# Receiver-Sheet.net
KiCad netlist of a schematic drawn in Altium Designer
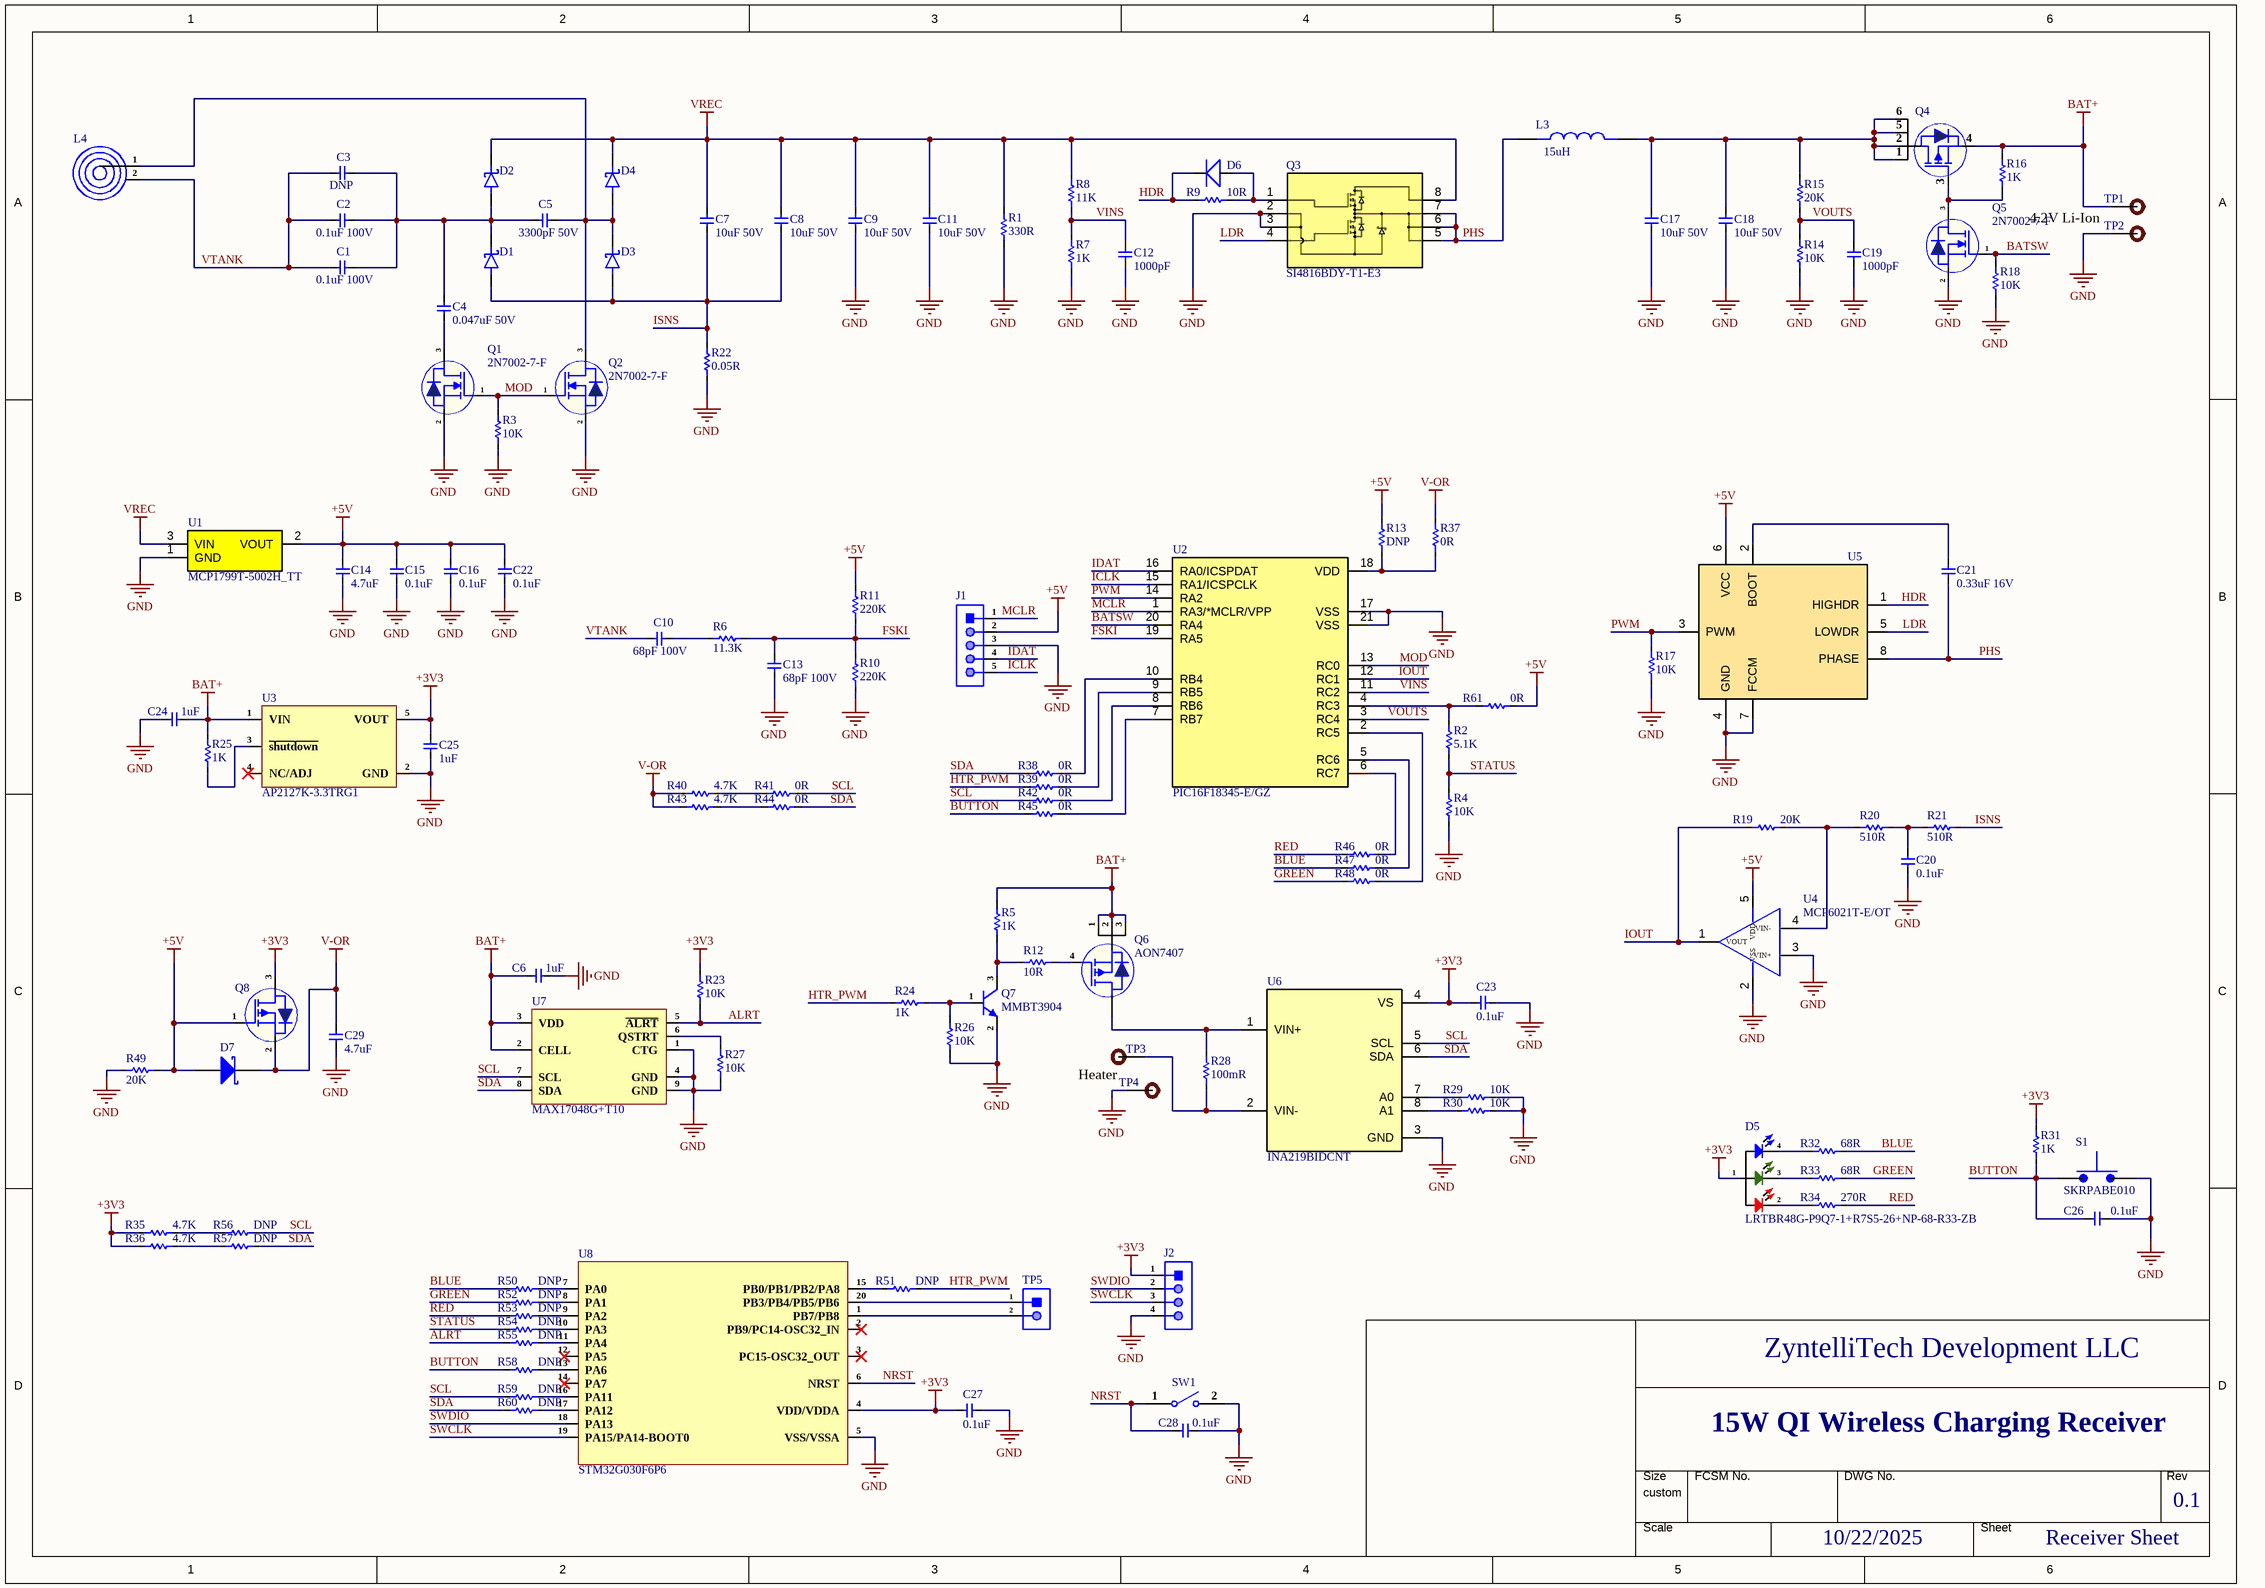
[diagram p0: Receiver-Sheet.SchDoc]

(export (version "E")
  (design (tool "Eeschema 10.0.6"))
  (components
    (comp (ref "C1")
      (value "0.1uF 100V")
      (footprint "Cap-1206")
      (description "CC1206KKX7R0BB104 - CAP CER 0.1uF 100V 10% X7R SMD 1206")
      (libsource (lib "Schlib1") (part "CAP-1206"))
    )
    (comp (ref "C2")
      (value "0.1uF 100V")
      (footprint "Cap-1206")
      (description "CC1206KKX7R0BB104 - CAP CER 0.1uF 100V 10% X7R SMD 1206")
      (libsource (lib "Schlib1") (part "CAP-1206"))
    )
    (comp (ref "C3")
      (value "DNP")
      (footprint "Cap-1206")
      (description "CC1206KKX7R0BB104 - CAP CER 0.1uF 100V 10% X7R SMD 1206")
      (libsource (lib "Schlib1") (part "CAP-1206"))
    )
    (comp (ref "C4")
      (value "0.047uF 50V")
      (footprint "Cap-0805")
      (description "C0805C473K5RACTU - CAP CER 0.047uF 50V 10% X7R SMD 0805")
      (libsource (lib "Schlib1") (part "CAP-0805"))
    )
    (comp (ref "C5")
      (value "3300pF 50V")
      (footprint "Cap-0805")
      (description "885012007066 - CAP CER 3300pF 50V 5% NP0 SMD 0805")
      (libsource (lib "Schlib1") (part "CAP-0805"))
    )
    (comp (ref "C6") (value "1uF") (footprint "Cap-0603") (libsource (lib "Schlib1") (part "CAP-0603")))
    (comp (ref "C7")
      (value "10uF 50V")
      (footprint "Cap-1210")
      (description "UMK325AB7106MM - CAP CER 10uF 50V 20% X7R SMD 1210")
      (libsource (lib "Schlib1") (part "CAP-1210"))
    )
    (comp (ref "C8")
      (value "10uF 50V")
      (footprint "Cap-1210")
      (description "UMK325AB7106MM - CAP CER 10uF 50V 20% X7R SMD 1210")
      (libsource (lib "Schlib1") (part "CAP-1210"))
    )
    (comp (ref "C9")
      (value "10uF 50V")
      (footprint "Cap-1210")
      (description "UMK325AB7106MM - CAP CER 10uF 50V 20% X7R SMD 1210")
      (libsource (lib "Schlib1") (part "CAP-1210"))
    )
    (comp (ref "C10")
      (value "68pF 100V")
      (footprint "Cap-0603")
      (description "C0603C680J1GACTU - CAP CER 68pF 100V 5% C0G SMD 0603")
      (libsource (lib "Schlib1") (part "CAP-0603"))
    )
    (comp (ref "C11")
      (value "10uF 50V")
      (footprint "Cap-1210")
      (description "UMK325AB7106MM - CAP CER 10uF 50V 20% X7R SMD 1210")
      (libsource (lib "Schlib1") (part "CAP-1210"))
    )
    (comp (ref "C12")
      (value "1000pF")
      (footprint "Cap-0603")
      (description "NMC0603X7R102K50TRPF - CAP CER 1000pF 50V 20% X7R SMD 0603")
      (libsource (lib "Schlib1") (part "CAP-0603"))
    )
    (comp (ref "C13")
      (value "68pF 100V")
      (footprint "Cap-0603")
      (description "C0603C680J1GACTU - CAP CER 68pF 100V 5% C0G SMD 0603")
      (libsource (lib "Schlib1") (part "CAP-0603"))
    )
    (comp (ref "C14")
      (value "4.7uF")
      (footprint "Cap-0805")
      (description "C2012X5R1E475M125AB - CAP CER 4.7uF 25V 20% X5R SMD 0805")
      (libsource (lib "Schlib1") (part "CAP-0805"))
    )
    (comp (ref "C15")
      (value "0.1uF")
      (footprint "Cap-0603")
      (description "06033C104JAT2A - CAP CER 0.1uF 25V 5% X7R SMD 0603")
      (libsource (lib "Schlib1") (part "CAP-0603"))
    )
    (comp (ref "C16")
      (value "0.1uF")
      (footprint "Cap-0603")
      (description "06033C104JAT2A - CAP CER 0.1uF 25V 5% X7R SMD 0603")
      (libsource (lib "Schlib1") (part "CAP-0603"))
    )
    (comp (ref "C17")
      (value "10uF 50V")
      (footprint "Cap-1210")
      (description "UMK325AB7106MM - CAP CER 10uF 50V 20% X7R SMD 1210")
      (libsource (lib "Schlib1") (part "CAP-1210"))
    )
    (comp (ref "C18")
      (value "10uF 50V")
      (footprint "Cap-1210")
      (description "UMK325AB7106MM - CAP CER 10uF 50V 20% X7R SMD 1210")
      (libsource (lib "Schlib1") (part "CAP-1210"))
    )
    (comp (ref "C19")
      (value "1000pF")
      (footprint "Cap-0603")
      (description "NMC0603X7R102K50TRPF - CAP CER 1000pF 50V 20% X7R SMD 0603")
      (libsource (lib "Schlib1") (part "CAP-0603"))
    )
    (comp (ref "C20")
      (value "0.1uF")
      (footprint "Cap-0603")
      (description "CL10B104KO8NNNC - CAP CER 0.1uF 16V 10% X7R SMD 0603")
      (libsource (lib "Schlib1") (part "CAP-0603"))
    )
    (comp (ref "C21")
      (value "0.33uF 16V")
      (footprint "Cap-0603")
      (description "885012206049 - CAP CER 0.33uF 16V 10% X7R SMD 0603")
      (libsource (lib "Schlib1") (part "CAP-0603"))
    )
    (comp (ref "C22")
      (value "0.1uF")
      (footprint "Cap-0603")
      (description "06033C104JAT2A - CAP CER 0.1uF 25V 5% X7R SMD 0603")
      (libsource (lib "Schlib1") (part "CAP-0603"))
    )
    (comp (ref "C23")
      (value "0.1uF")
      (footprint "Cap-0603")
      (description "CL10B104KO8NNNC - CAP CER 0.1uF 16V 10% X7R SMD 0603")
      (libsource (lib "Schlib1") (part "CAP-0603"))
    )
    (comp (ref "C24") (value "1uF") (footprint "Cap-0603") (libsource (lib "Schlib1") (part "CAP-0603")))
    (comp (ref "C25") (value "1uF") (footprint "Cap-0603") (libsource (lib "Schlib1") (part "CAP-0603")))
    (comp (ref "C26")
      (value "0.1uF")
      (footprint "Cap-0603")
      (description "06033C104JAT2A - CAP CER 0.1uF 25V 5% X7R SMD 0603")
      (libsource (lib "Schlib1") (part "CAP-0603"))
    )
    (comp (ref "C27")
      (value "0.1uF")
      (footprint "Cap-0603")
      (description "CL10B104KO8NNNC - CAP CER 0.1uF 16V 10% X7R SMD 0603")
      (libsource (lib "Schlib1") (part "CAP-0603"))
    )
    (comp (ref "C28")
      (value "0.1uF")
      (footprint "Cap-0603")
      (description "CL10B104KO8NNNC - CAP CER 0.1uF 16V 10% X7R SMD 0603")
      (libsource (lib "Schlib1") (part "CAP-0603"))
    )
    (comp (ref "C29")
      (value "4.7uF")
      (footprint "Cap-0805")
      (description "C2012X5R1E475M125AB - CAP CER 4.7uF 25V 20% X5R SMD 0805")
      (libsource (lib "Schlib1") (part "CAP-0805"))
    )
    (comp (ref "D1")
      (value "PMEG6045ETPX")
      (footprint "DIO_PMEG6045ETPX")
      (description "Rectifier Diode Schottky 4.5A 20ns Automotive 2-Pin SOD-128 T/R")
      (fields (field (name "MF") "Nexperia"))
      (libsource (lib "Schlib1") (part "PMEG6045ETPX"))
    )
    (comp (ref "D2")
      (value "PMEG6045ETPX")
      (footprint "DIO_PMEG6045ETPX")
      (description "Rectifier Diode Schottky 4.5A 20ns Automotive 2-Pin SOD-128 T/R")
      (fields (field (name "MF") "Nexperia"))
      (libsource (lib "Schlib1") (part "PMEG6045ETPX"))
    )
    (comp (ref "D3")
      (value "PMEG6045ETPX")
      (footprint "DIO_PMEG6045ETPX")
      (description "Rectifier Diode Schottky 4.5A 20ns Automotive 2-Pin SOD-128 T/R")
      (fields (field (name "MF") "Nexperia"))
      (libsource (lib "Schlib1") (part "PMEG6045ETPX"))
    )
    (comp (ref "D4")
      (value "PMEG6045ETPX")
      (footprint "DIO_PMEG6045ETPX")
      (description "Rectifier Diode Schottky 4.5A 20ns Automotive 2-Pin SOD-128 T/R")
      (fields (field (name "MF") "Nexperia"))
      (libsource (lib "Schlib1") (part "PMEG6045ETPX"))
    )
    (comp (ref "D5")
      (value "LRTBR48G-P9Q7-1+R7S5-26+NP-68-R33-ZB")
      (footprint "LRTBR48G-P9Q7-1+R7S5-26+NP-68-R33-ZB")
      (libsource (lib "Schlib1") (part "LRTBR48G-P9Q7-1+R7S5-26+NP-68-R33-ZB"))
    )
    (comp (ref "D6")
      (value "BAT54JFILM")
      (footprint "SOD-323")
      (fields (field (name "MF") "STMicroelectronics"))
      (libsource (lib "Schlib1") (part "BAT54JFILM"))
    )
    (comp (ref "D7")
      (value "MBR120VLSFT3G")
      (footprint "SOD-123")
      (description "DIODE SCHOTTKY 20V 1A SOD123FL")
      (fields (field (name "MANUFACTURER") "ON Semiconductor") (field (name "LCSC PART NUMBER") "C295749"))
      (libsource (lib "Schlib1") (part "MBR120VLSFT3G"))
    )
    (comp (ref "J1")
      (value "X6511WV-05H-C60D30")
      (footprint "HDR1X5_")
      (fields (field (name "MANUFACTURER") "XKB") (field (name "LCSC PART NUMBER") "C706877"))
      (libsource (lib "Schlib1") (part "X6511WV-05H-C60D30"))
    )
    (comp (ref "J2")
      (value "X6511WV-04H-C60D30")
      (footprint "HDR1X4_")
      (fields (field (name "MANUFACTURER") "XKB") (field (name "LCSC PART NUMBER") "C706876"))
      (libsource (lib "Schlib1") (part "X6511WV-04H-C60D30"))
    )
    (comp (ref "L3")
      (value "15uH")
      (footprint "IND_XAL6060-153MEB")
      (description "Power inductor, shielded, 20% tol, SMT, RoHS, halogen f")
      (fields (field (name "MF") "Coilcraft") (field (name "MP") "XAL6060-153MEB"))
      (libsource (lib "Schlib1") (part "XAL6060-153MEB"))
    )
    (comp (ref "L4")
      (value "760308102207")
      (footprint "WE-WPCC_RX_760308102207")
      (description "RX 1 COIL 1 LYR BIFILAR 8UH 5A")
      (fields (field (name "MF") "WÃ¼rth Elektronik"))
      (libsource (lib "Schlib1") (part "760308102207"))
    )
    (comp (ref "Q1")
      (value "2N7002-7-F")
      (footprint "SOT103P240X110-3N")
      (description "N-Channel 60 V 115mA (Ta) 370mW (Ta) Surface Mount SOT-23-3")
      (fields (field (name "MF") "Diodes Inc."))
      (libsource (lib "Schlib1") (part "2N7002-7-F"))
    )
    (comp (ref "Q2")
      (value "2N7002-7-F")
      (footprint "SOT103P240X110-3N")
      (description "N-Channel 60 V 115mA (Ta) 370mW (Ta) Surface Mount SOT-23-3")
      (fields (field (name "MF") "Diodes Inc."))
      (libsource (lib "Schlib1") (part "2N7002-7-F"))
    )
    (comp (ref "Q3")
      (value "SI4816BDY-T1-E3")
      (footprint "SOIC8_NARROW_VIS")
      (description "DUAL N-CH 30-V (D-S) MOSFET W/SCHOTTKY")
      (libsource (lib "Schlib1") (part "SI4816BDY-T1-E3"))
    )
    (comp (ref "Q4")
      (value "SI3433CDV-T1-GE3")
      (footprint "6-TSOP_")
      (libsource (lib "Schlib1") (part "SI3433CDV-T1-GE3"))
    )
    (comp (ref "Q5")
      (value "2N7002-7-F")
      (footprint "SOT103P240X110-3N")
      (description "N-Channel 60 V 115mA (Ta) 370mW (Ta) Surface Mount SOT-23-3")
      (fields (field (name "MF") "Diodes Inc."))
      (libsource (lib "Schlib1") (part "2N7002-7-F"))
    )
    (comp (ref "Q6")
      (value "AON7407")
      (footprint "TRANS_AON7407")
      (description "P-Channel 20 V 14.5A (Ta), 40A (Tc) 3.1W (Ta), 29W (Tc) Surface Mount 8-DFN-EP (3x3)")
      (fields (field (name "MF") "Alpha & Omega Semiconductor Inc."))
      (libsource (lib "Schlib1") (part "AON7407"))
    )
    (comp (ref "Q7")
      (value "MMBT3904")
      (footprint "SOT-23")
      (description "40V 200mW 100 200mA NPN SOT-23 Bipolar (BJT) ROHS")
      (fields (field (name "MANUFACTURER") "ElecSuper") (field (name "LCSC PART NUMBER") "C5249683"))
      (libsource (lib "Schlib1") (part "MMBT3904"))
    )
    (comp (ref "Q8")
      (value "DMG3415U")
      (footprint "SOT-23")
      (description "P-Channel MOSFETs ROHS")
      (fields (field (name "MANUFACTURER") "TECH PUBLIC") (field (name "LCSC PART NUMBER") "C7202986"))
      (libsource (lib "Schlib1") (part "DMG3415U"))
    )
    (comp (ref "R1")
      (value "330R")
      (footprint "Res-1206")
      (description "CRCW1206330RFKTA - RES TKF 330R 1% 1/4W SMD 1206")
      (libsource (lib "Schlib1") (part "RES-1206"))
    )
    (comp (ref "R2") (value "5.1K") (footprint "Res-0603") (libsource (lib "Schlib1") (part "RES-0603")))
    (comp (ref "R3")
      (value "10K")
      (footprint "Res-0603")
      (description "CPF0603F10KC1 - RES TF 10k 1% 1/16W SMD 0603")
      (libsource (lib "Schlib1") (part "RES-0603"))
    )
    (comp (ref "R4")
      (value "10K")
      (footprint "Res-0603")
      (description "CPF0603F10KC1 - RES TF 10k 1% 1/16W SMD 0603")
      (libsource (lib "Schlib1") (part "RES-0603"))
    )
    (comp (ref "R5")
      (value "1K")
      (footprint "Res-0603")
      (description "RMCF0603FT1K00 - RES TKF 1k 1% 1/10W SMD 0603")
      (libsource (lib "Schlib1") (part "RES-0603"))
    )
    (comp (ref "R6")
      (value "11.3K")
      (footprint "Res-0603")
      (description "CRCW060311K3FKEA - RES TKF 11.3k 1% 1/10W SMD 0603")
      (libsource (lib "Schlib1") (part "RES-0603"))
    )
    (comp (ref "R7")
      (value "1K")
      (footprint "Res-0603")
      (description "MC0063W060311K - RES TKF 1k 1% 1/16W SMD 0603")
      (libsource (lib "Schlib1") (part "RES-0603"))
    )
    (comp (ref "R8")
      (value "11K")
      (footprint "Res-0603")
      (description "ERJ-3EKF1102V - RES TKF 11k 1% 1/10W SMD 0603")
      (libsource (lib "Schlib1") (part "RES-0603"))
    )
    (comp (ref "R9")
      (value "10R")
      (footprint "Res-0603")
      (description "ERJ3EKF10R0V - RES TKF 10R 1% 1/10W SMD 0603")
      (libsource (lib "Schlib1") (part "RES-0603"))
    )
    (comp (ref "R10")
      (value "220K")
      (footprint "Res-0603")
      (description "ERJ-3EKF2203V - RES TKF 220k 1% 1/10W SMD 0603")
      (libsource (lib "Schlib1") (part "RES-0603"))
    )
    (comp (ref "R11")
      (value "220K")
      (footprint "Res-0603")
      (description "ERJ-3EKF2203V - RES TKF 220k 1% 1/10W SMD 0603")
      (libsource (lib "Schlib1") (part "RES-0603"))
    )
    (comp (ref "R12")
      (value "10R")
      (footprint "Res-0603")
      (description "RC0603FR-0710RL - 10R 0603")
      (libsource (lib "Schlib1") (part "RES-0603"))
    )
    (comp (ref "R13")
      (value "DNP")
      (footprint "Res-0603")
      (description "0R")
      (libsource (lib "Schlib1") (part "RES-0603"))
    )
    (comp (ref "R14")
      (value "10K")
      (footprint "Res-0603")
      (description "CPF0603F10KC1 - RES TF 10k 1% 1/16W SMD 0603")
      (libsource (lib "Schlib1") (part "RES-0603"))
    )
    (comp (ref "R15")
      (value "20K")
      (footprint "Res-0603")
      (description "RC0603FR-0720KL - RES TKF 20k 1% 1/10W SMD 0603")
      (libsource (lib "Schlib1") (part "RES-0603"))
    )
    (comp (ref "R16")
      (value "1K")
      (footprint "Res-0603")
      (description "RMCF0603FT1K00 - RES TKF 1k 1% 1/10W SMD 0603")
      (libsource (lib "Schlib1") (part "RES-0603"))
    )
    (comp (ref "R17")
      (value "10K")
      (footprint "Res-0603")
      (description "CPF0603F10KC1 - RES TF 10k 1% 1/16W SMD 0603")
      (libsource (lib "Schlib1") (part "RES-0603"))
    )
    (comp (ref "R18")
      (value "10K")
      (footprint "Res-0603")
      (description "CPF0603F10KC1 - RES TF 10k 1% 1/16W SMD 0603")
      (libsource (lib "Schlib1") (part "RES-0603"))
    )
    (comp (ref "R19")
      (value "20K")
      (footprint "Res-0603")
      (description "RC0603FR-0720KL - RES TKF 20k 1% 1/10W SMD 0603")
      (libsource (lib "Schlib1") (part "RES-0603"))
    )
    (comp (ref "R20")
      (value "510R")
      (footprint "Res-0603")
      (description "CRCW0603510RFKEA - RES TKF 510R 1% 1/10W SMD 0603")
      (libsource (lib "Schlib1") (part "RES-0603"))
    )
    (comp (ref "R21")
      (value "510R")
      (footprint "Res-0603")
      (description "CRCW0603510RFKEA - RES TKF 510R 1% 1/10W SMD 0603")
      (libsource (lib "Schlib1") (part "RES-0603"))
    )
    (comp (ref "R22")
      (value "0.05R")
      (footprint "Res-1206")
      (description "WSLP1206R0500FEA - RES MS 0.05R 1% 1W SMD 1206")
      (libsource (lib "Schlib1") (part "RES-1206"))
    )
    (comp (ref "R23")
      (value "10K")
      (footprint "Res-0603")
      (description "CPF0603F10KC1 - RES TF 10k 1% 1/16W SMD 0603")
      (libsource (lib "Schlib1") (part "RES-0603"))
    )
    (comp (ref "R24")
      (value "1K")
      (footprint "Res-0603")
      (description "RMCF0603FT1K00 - RES TKF 1k 1% 1/10W SMD 0603")
      (libsource (lib "Schlib1") (part "RES-0603"))
    )
    (comp (ref "R25")
      (value "1K")
      (footprint "Res-0603")
      (description "RMCF0603FT1K00 - RES TKF 1k 1% 1/10W SMD 0603")
      (libsource (lib "Schlib1") (part "RES-0603"))
    )
    (comp (ref "R26")
      (value "10K")
      (footprint "Res-0603")
      (description "CPF0603F10KC1 - RES TF 10k 1% 1/16W SMD 0603")
      (libsource (lib "Schlib1") (part "RES-0603"))
    )
    (comp (ref "R27")
      (value "10K")
      (footprint "Res-0603")
      (description "CPF0603F10KC1 - RES TF 10k 1% 1/16W SMD 0603")
      (libsource (lib "Schlib1") (part "RES-0603"))
    )
    (comp (ref "R28")
      (value "100mR")
      (footprint "RES-2512")
      (description "CRA2512-FZ-R100ELF - RES 0.1 OHM 1% 3W 2512")
      (libsource (lib "Schlib1") (part "RES-2512"))
    )
    (comp (ref "R29")
      (value "10K")
      (footprint "Res-0603")
      (description "CPF0603F10KC1 - RES TF 10k 1% 1/16W SMD 0603")
      (libsource (lib "Schlib1") (part "RES-0603"))
    )
    (comp (ref "R30")
      (value "10K")
      (footprint "Res-0603")
      (description "CPF0603F10KC1 - RES TF 10k 1% 1/16W SMD 0603")
      (libsource (lib "Schlib1") (part "RES-0603"))
    )
    (comp (ref "R31")
      (value "1K")
      (footprint "Res-0603")
      (description "RMCF0603FT1K00 - RES TKF 1k 1% 1/10W SMD 0603")
      (libsource (lib "Schlib1") (part "RES-0603"))
    )
    (comp (ref "R32") (value "68R") (footprint "Res-0603") (libsource (lib "Schlib1") (part "RES-0603")))
    (comp (ref "R33") (value "68R") (footprint "Res-0603") (libsource (lib "Schlib1") (part "RES-0603")))
    (comp (ref "R34") (value "270R") (footprint "Res-0603") (libsource (lib "Schlib1") (part "RES-0603")))
    (comp (ref "R35") (value "4.7K") (footprint "Res-0603") (libsource (lib "Schlib1") (part "RES-0603")))
    (comp (ref "R36") (value "4.7K") (footprint "Res-0603") (libsource (lib "Schlib1") (part "RES-0603")))
    (comp (ref "R37") (value "0R") (footprint "Res-0603") (libsource (lib "Schlib1") (part "RES-0603")))
    (comp (ref "R38") (value "0R") (footprint "Res-0603") (libsource (lib "Schlib1") (part "RES-0603")))
    (comp (ref "R39") (value "0R") (footprint "Res-0603") (libsource (lib "Schlib1") (part "RES-0603")))
    (comp (ref "R40") (value "4.7K") (footprint "Res-0603") (libsource (lib "Schlib1") (part "RES-0603")))
    (comp (ref "R41") (value "0R") (footprint "Res-0603") (libsource (lib "Schlib1") (part "RES-0603")))
    (comp (ref "R42") (value "0R") (footprint "Res-0603") (libsource (lib "Schlib1") (part "RES-0603")))
    (comp (ref "R43") (value "4.7K") (footprint "Res-0603") (libsource (lib "Schlib1") (part "RES-0603")))
    (comp (ref "R44") (value "0R") (footprint "Res-0603") (libsource (lib "Schlib1") (part "RES-0603")))
    (comp (ref "R45") (value "0R") (footprint "Res-0603") (libsource (lib "Schlib1") (part "RES-0603")))
    (comp (ref "R46") (value "0R") (footprint "Res-0603") (libsource (lib "Schlib1") (part "RES-0603")))
    (comp (ref "R47") (value "0R") (footprint "Res-0603") (libsource (lib "Schlib1") (part "RES-0603")))
    (comp (ref "R48") (value "0R") (footprint "Res-0603") (libsource (lib "Schlib1") (part "RES-0603")))
    (comp (ref "R49")
      (value "20K")
      (footprint "Res-0603")
      (description "RC0603FR-0720KL - RES TKF 20k 1% 1/10W SMD 0603")
      (libsource (lib "Schlib1") (part "RES-0603"))
    )
    (comp (ref "R50")
      (value "DNP")
      (footprint "Res-0603")
      (description "0R")
      (libsource (lib "Schlib1") (part "RES-0603"))
    )
    (comp (ref "R51")
      (value "DNP")
      (footprint "Res-0603")
      (description "0R")
      (libsource (lib "Schlib1") (part "RES-0603"))
    )
    (comp (ref "R52")
      (value "DNP")
      (footprint "Res-0603")
      (description "0R")
      (libsource (lib "Schlib1") (part "RES-0603"))
    )
    (comp (ref "R53")
      (value "DNP")
      (footprint "Res-0603")
      (description "0R")
      (libsource (lib "Schlib1") (part "RES-0603"))
    )
    (comp (ref "R54")
      (value "DNP")
      (footprint "Res-0603")
      (description "0R")
      (libsource (lib "Schlib1") (part "RES-0603"))
    )
    (comp (ref "R55")
      (value "DNP")
      (footprint "Res-0603")
      (description "0R")
      (libsource (lib "Schlib1") (part "RES-0603"))
    )
    (comp (ref "R56")
      (value "DNP")
      (footprint "Res-0603")
      (description "0R")
      (libsource (lib "Schlib1") (part "RES-0603"))
    )
    (comp (ref "R57")
      (value "DNP")
      (footprint "Res-0603")
      (description "0R")
      (libsource (lib "Schlib1") (part "RES-0603"))
    )
    (comp (ref "R58")
      (value "DNP")
      (footprint "Res-0603")
      (description "0R")
      (libsource (lib "Schlib1") (part "RES-0603"))
    )
    (comp (ref "R59")
      (value "DNP")
      (footprint "Res-0603")
      (description "0R")
      (libsource (lib "Schlib1") (part "RES-0603"))
    )
    (comp (ref "R60")
      (value "DNP")
      (footprint "Res-0603")
      (description "0R")
      (libsource (lib "Schlib1") (part "RES-0603"))
    )
    (comp (ref "R61") (value "0R") (footprint "Res-0603") (libsource (lib "Schlib1") (part "RES-0603")))
    (comp (ref "S1")
      (value "SKRPABE010")
      (footprint "SW_SKRPABE010")
      (description "Switch Tactile N.O. SPST Button J-Bend 0.05A 16VDC 1.57N SMD Automotive T/R")
      (fields (field (name "MF") "ALPS"))
      (libsource (lib "Schlib1") (part "SKRPABE010"))
    )
    (comp (ref "SW1")
      (value "B3U-1000P")
      (footprint "B3U-1000P")
      (description "SWITCH TACTILE SPST-NO 0.05A 12V")
      (fields (field (name "MANUFACTURER") "Omron") (field (name "LCSC PART NUMBER") "C231329"))
      (libsource (lib "Schlib1") (part "B3U-1000P"))
    )
    (comp (ref "TP1")
      (value "0.5mm Test Pad")
      (footprint "0.5mm Test Pad")
      (description "Test pad")
      (libsource (lib "Schlib1") (part "0.5mm Test Pad"))
    )
    (comp (ref "TP2")
      (value "0.5mm Test Pad")
      (footprint "0.5mm Test Pad")
      (description "Test pad")
      (libsource (lib "Schlib1") (part "0.5mm Test Pad"))
    )
    (comp (ref "TP3")
      (value "0.5mm Test Pad")
      (footprint "0.5mm Test Pad")
      (description "Test pad")
      (libsource (lib "Schlib1") (part "0.5mm Test Pad"))
    )
    (comp (ref "TP4")
      (value "0.5mm Test Pad")
      (footprint "0.5mm Test Pad")
      (description "Test pad")
      (libsource (lib "Schlib1") (part "0.5mm Test Pad"))
    )
    (comp (ref "TP5")
      (value "2 Test Pad")
      (footprint "2 Test Pad")
      (description "Wire Connecting Pad")
      (libsource (lib "Schlib1") (part "2 Test Pad"))
    )
    (comp (ref "U1")
      (value "MCP1799T-5002H_TT")
      (footprint "SOT95P237X112-3N")
      (description "Linear Voltage Regulator IC Positive Fixed 1 Output  80mA SOT-23-3")
      (fields (field (name "MF") "Microchip Technology") (field (name "MP") "MCP1799T-5002H/TT"))
      (libsource (lib "Schlib1") (part "MCP1799T-5002H_TT"))
    )
    (comp (ref "U2")
      (value "PIC16F18345-E/GZ")
      (footprint "UQFN20_GZ_MCH")
      (description "No Description Available")
      (libsource (lib "Schlib1") (part "PIC16F18345-EGZ"))
    )
    (comp (ref "U3")
      (value "AP2127K-3.3TRG1")
      (footprint "SOT-23-5")
      (description "IC REG LINEAR 3.3V 300MA SOT23-5")
      (fields (field (name "LCSC PART NUMBER") "C156285") (field (name "MANUFACTURER") "Diodes"))
      (libsource (lib "Schlib1") (part "AP2127K-3.3TRG1"))
    )
    (comp (ref "U4")
      (value "MCP6021T-E/OT")
      (footprint "SOT95P270X145-5N")
      (description "IC OPAMP GP 1 CIRCUIT SOT23-5")
      (fields (field (name "MF") "Microchip Technology"))
      (libsource (lib "Schlib1") (part "MCP6021T-E/OT"))
    )
    (comp (ref "U5")
      (value "MCP14628-E/SN")
      (footprint "SOIC127P600X175-8N")
      (fields (field (name "MF") "Microchip"))
      (libsource (lib "Schlib1") (part "MCP14628-E/SN"))
    )
    (comp (ref "U6")
      (value "INA219BIDCNT")
      (footprint "SOT65P280X145-8N")
      (description "26-V 12-bit I2C output digital power monitor")
      (fields (field (name "MF") "Texas Instruments"))
      (libsource (lib "Schlib1") (part "INA219BIDCNT"))
    )
    (comp (ref "U7")
      (value "MAX17048G+T10")
      (footprint "8-TDFN-EP (2x2)")
      (description "IC BATT MON LI-ION 1CELL 8TDFN")
      (fields (field (name "MANUFACTURER") "Maxim") (field (name "LCSC PART NUMBER") "C2682616"))
      (libsource (lib "Schlib1") (part "MAX17048G+T10"))
    )
    (comp (ref "U8")
      (value "STM32G030F6P6")
      (footprint "TSSOP-20")
      (description "IC MCU 32BIT 32KB FLASH 20TSSOP")
      (fields (field (name "LCSC PART NUMBER") "C724040") (field (name "MANUFACTURER") "STMicroelectronics"))
      (libsource (lib "Schlib1") (part "STM32G030F6P6"))
    )
  )
  (nets
    (net (code "1") (name "+3V3") (class "Default")
      (node (ref "C23") (pin "2") (pinfunction "2_2") (pintype "passive"))
      (node (ref "C25") (pin "1") (pinfunction "1_1") (pintype "passive"))
      (node (ref "C27") (pin "2") (pinfunction "2_2") (pintype "passive"))
      (node (ref "D5") (pin "1") (pinfunction "+_1") (pintype "passive"))
      (node (ref "J2") (pin "1") (pinfunction "1_1") (pintype "passive"))
      (node (ref "Q8") (pin "3") (pinfunction "D_3") (pintype "passive"))
      (node (ref "R23") (pin "1") (pinfunction "1_1") (pintype "passive"))
      (node (ref "R31") (pin "1") (pinfunction "1_1") (pintype "passive"))
      (node (ref "R35") (pin "2") (pinfunction "2_2") (pintype "passive"))
      (node (ref "R36") (pin "2") (pinfunction "2_2") (pintype "passive"))
      (node (ref "U3") (pin "5") (pinfunction "VOUT_5") (pintype "passive"))
      (node (ref "U6") (pin "4") (pinfunction "VS_4") (pintype "passive"))
      (node (ref "U8") (pin "4") (pinfunction "VDD/VDDA_4") (pintype "passive"))
    )
    (net (code "2") (name "+5V") (class "Default")
      (node (ref "C14") (pin "2") (pinfunction "2_2") (pintype "passive"))
      (node (ref "C15") (pin "2") (pinfunction "2_2") (pintype "passive"))
      (node (ref "C16") (pin "2") (pinfunction "2_2") (pintype "passive"))
      (node (ref "C22") (pin "2") (pinfunction "2_2") (pintype "passive"))
      (node (ref "D7") (pin "1") (pinfunction "A_1") (pintype "passive"))
      (node (ref "J1") (pin "2") (pinfunction "2_2") (pintype "passive"))
      (node (ref "Q8") (pin "1") (pinfunction "G_1") (pintype "passive"))
      (node (ref "R11") (pin "2") (pinfunction "2_2") (pintype "passive"))
      (node (ref "R13") (pin "2") (pinfunction "2_2") (pintype "passive"))
      (node (ref "R49") (pin "1") (pinfunction "1_1") (pintype "passive"))
      (node (ref "R61") (pin "1") (pinfunction "1_1") (pintype "passive"))
      (node (ref "U1") (pin "2") (pinfunction "VOUT_2") (pintype "passive"))
      (node (ref "U4") (pin "5") (pinfunction "VDD_5") (pintype "passive"))
      (node (ref "U5") (pin "6") (pinfunction "VCC_6") (pintype "passive"))
    )
    (net (code "3") (name "/ALRT") (class "Default")
      (node (ref "R23") (pin "2") (pinfunction "2_2") (pintype "passive"))
      (node (ref "R55") (pin "1") (pinfunction "1_1") (pintype "passive"))
      (node (ref "U7") (pin "5") (pinfunction "~{ALRT}_5") (pintype "passive"))
    )
    (net (code "4") (name "/BATSW") (class "Default")
      (node (ref "Q5") (pin "1") (pinfunction "G_1") (pintype "passive"))
      (node (ref "R18") (pin "2") (pinfunction "2_2") (pintype "passive"))
      (node (ref "U2") (pin "20") (pinfunction "RA4_20") (pintype "passive"))
    )
    (net (code "5") (name "/BLUE") (class "Default")
      (node (ref "R32") (pin "2") (pinfunction "2_2") (pintype "passive"))
      (node (ref "R47") (pin "2") (pinfunction "2_2") (pintype "passive"))
      (node (ref "R50") (pin "1") (pinfunction "1_1") (pintype "passive"))
    )
    (net (code "6") (name "/BUTTON") (class "Default")
      (node (ref "C26") (pin "2") (pinfunction "2_2") (pintype "passive"))
      (node (ref "R31") (pin "2") (pinfunction "2_2") (pintype "passive"))
      (node (ref "R45") (pin "2") (pinfunction "2_2") (pintype "passive"))
      (node (ref "R58") (pin "1") (pinfunction "1_1") (pintype "passive"))
      (node (ref "S1") (pin "1") (pinfunction "1_1") (pintype "passive"))
    )
    (net (code "7") (name "/FSKI") (class "Default")
      (node (ref "C13") (pin "2") (pinfunction "2_2") (pintype "passive"))
      (node (ref "R10") (pin "2") (pinfunction "2_2") (pintype "passive"))
      (node (ref "R11") (pin "1") (pinfunction "1_1") (pintype "passive"))
      (node (ref "R6") (pin "1") (pinfunction "1_1") (pintype "passive"))
      (node (ref "U2") (pin "19") (pinfunction "RA5_19") (pintype "passive"))
    )
    (net (code "8") (name "/GREEN") (class "Default")
      (node (ref "R33") (pin "2") (pinfunction "2_2") (pintype "passive"))
      (node (ref "R48") (pin "2") (pinfunction "2_2") (pintype "passive"))
      (node (ref "R52") (pin "1") (pinfunction "1_1") (pintype "passive"))
    )
    (net (code "9") (name "/HDR") (class "Default")
      (node (ref "D6") (pin "NEG") (pinfunction "NEG_NEG") (pintype "passive"))
      (node (ref "R9") (pin "1") (pinfunction "1_1") (pintype "passive"))
      (node (ref "U5") (pin "1") (pinfunction "HIGHDR_1") (pintype "passive"))
    )
    (net (code "10") (name "/HTR_PWM") (class "Default")
      (node (ref "R24") (pin "2") (pinfunction "2_2") (pintype "passive"))
      (node (ref "R39") (pin "2") (pinfunction "2_2") (pintype "passive"))
      (node (ref "R51") (pin "2") (pinfunction "2_2") (pintype "passive"))
    )
    (net (code "11") (name "/ICLK") (class "Default")
      (node (ref "J1") (pin "5") (pinfunction "5_5") (pintype "passive"))
      (node (ref "U2") (pin "15") (pinfunction "RA1/ICSPCLK_15") (pintype "passive"))
    )
    (net (code "12") (name "/IDAT") (class "Default")
      (node (ref "J1") (pin "4") (pinfunction "4_4") (pintype "passive"))
      (node (ref "U2") (pin "16") (pinfunction "RA0/ICSPDAT_16") (pintype "passive"))
    )
    (net (code "13") (name "/IOUT") (class "Default")
      (node (ref "R19") (pin "2") (pinfunction "2_2") (pintype "passive"))
      (node (ref "U2") (pin "12") (pinfunction "RC1_12") (pintype "passive"))
      (node (ref "U4") (pin "1") (pinfunction "VOUT_1") (pintype "passive"))
    )
    (net (code "14") (name "/ISNS") (class "Default")
      (node (ref "C7") (pin "1") (pinfunction "1_1") (pintype "passive"))
      (node (ref "C8") (pin "1") (pinfunction "1_1") (pintype "passive"))
      (node (ref "D1") (pin "A") (pinfunction "A_A") (pintype "passive"))
      (node (ref "D3") (pin "A") (pinfunction "A_A") (pintype "passive"))
      (node (ref "R21") (pin "2") (pinfunction "2_2") (pintype "passive"))
      (node (ref "R22") (pin "2") (pinfunction "2_2") (pintype "passive"))
    )
    (net (code "15") (name "/LDR") (class "Default")
      (node (ref "Q3") (pin "4") (pinfunction "4_4") (pintype "passive"))
      (node (ref "U5") (pin "5") (pinfunction "LOWDR_5") (pintype "passive"))
    )
    (net (code "16") (name "/MCLR") (class "Default")
      (node (ref "J1") (pin "1") (pinfunction "1_1") (pintype "passive"))
      (node (ref "U2") (pin "1") (pinfunction "RA3/*MCLR/VPP_1") (pintype "passive"))
    )
    (net (code "17") (name "/MOD") (class "Default")
      (node (ref "Q1") (pin "1") (pinfunction "G_1") (pintype "passive"))
      (node (ref "Q2") (pin "1") (pinfunction "G_1") (pintype "passive"))
      (node (ref "R3") (pin "2") (pinfunction "2_2") (pintype "passive"))
      (node (ref "U2") (pin "13") (pinfunction "RC0_13") (pintype "passive"))
    )
    (net (code "18") (name "/NRST") (class "Default")
      (node (ref "C28") (pin "2") (pinfunction "2_2") (pintype "passive"))
      (node (ref "SW1") (pin "1") (pinfunction "1_1") (pintype "passive"))
      (node (ref "U8") (pin "6") (pinfunction "NRST_6") (pintype "passive"))
    )
    (net (code "19") (name "/PHS") (class "Default")
      (node (ref "C21") (pin "1") (pinfunction "1_1") (pintype "passive"))
      (node (ref "L3") (pin "1") (pinfunction "1_1") (pintype "passive"))
      (node (ref "Q3") (pin "5") (pinfunction "5_5") (pintype "passive"))
      (node (ref "Q3") (pin "6") (pinfunction "6_6") (pintype "passive"))
      (node (ref "Q3") (pin "7") (pinfunction "7_7") (pintype "passive"))
      (node (ref "U5") (pin "8") (pinfunction "PHASE_8") (pintype "passive"))
    )
    (net (code "20") (name "/PWM") (class "Default")
      (node (ref "R17") (pin "2") (pinfunction "2_2") (pintype "passive"))
      (node (ref "U2") (pin "14") (pinfunction "RA2_14") (pintype "passive"))
      (node (ref "U5") (pin "3") (pinfunction "PWM_3") (pintype "passive"))
    )
    (net (code "21") (name "/RED") (class "Default")
      (node (ref "R34") (pin "2") (pinfunction "2_2") (pintype "passive"))
      (node (ref "R46") (pin "2") (pinfunction "2_2") (pintype "passive"))
      (node (ref "R53") (pin "1") (pinfunction "1_1") (pintype "passive"))
    )
    (net (code "22") (name "/SCL") (class "Default")
      (node (ref "R41") (pin "1") (pinfunction "1_1") (pintype "passive"))
      (node (ref "R42") (pin "2") (pinfunction "2_2") (pintype "passive"))
      (node (ref "R56") (pin "2") (pinfunction "2_2") (pintype "passive"))
      (node (ref "R59") (pin "1") (pinfunction "1_1") (pintype "passive"))
      (node (ref "U6") (pin "5") (pinfunction "SCL_5") (pintype "passive"))
      (node (ref "U7") (pin "7") (pinfunction "SCL_7") (pintype "passive"))
    )
    (net (code "23") (name "/SDA") (class "Default")
      (node (ref "R38") (pin "2") (pinfunction "2_2") (pintype "passive"))
      (node (ref "R44") (pin "1") (pinfunction "1_1") (pintype "passive"))
      (node (ref "R57") (pin "2") (pinfunction "2_2") (pintype "passive"))
      (node (ref "R60") (pin "1") (pinfunction "1_1") (pintype "passive"))
      (node (ref "U6") (pin "6") (pinfunction "SDA_6") (pintype "passive"))
      (node (ref "U7") (pin "8") (pinfunction "SDA_8") (pintype "passive"))
    )
    (net (code "24") (name "/STATUS") (class "Default")
      (node (ref "R2") (pin "1") (pinfunction "1_1") (pintype "passive"))
      (node (ref "R4") (pin "2") (pinfunction "2_2") (pintype "passive"))
      (node (ref "R54") (pin "1") (pinfunction "1_1") (pintype "passive"))
    )
    (net (code "25") (name "/SWCLK") (class "Default")
      (node (ref "J2") (pin "3") (pinfunction "3_3") (pintype "passive"))
      (node (ref "U8") (pin "19") (pinfunction "PA15/PA14-BOOT0_19") (pintype "passive"))
    )
    (net (code "26") (name "/SWDIO") (class "Default")
      (node (ref "J2") (pin "2") (pinfunction "2_2") (pintype "passive"))
      (node (ref "U8") (pin "18") (pinfunction "PA13_18") (pintype "passive"))
    )
    (net (code "27") (name "/VINS") (class "Default")
      (node (ref "C12") (pin "2") (pinfunction "2_2") (pintype "passive"))
      (node (ref "R7") (pin "2") (pinfunction "2_2") (pintype "passive"))
      (node (ref "R8") (pin "1") (pinfunction "1_1") (pintype "passive"))
      (node (ref "U2") (pin "11") (pinfunction "RC2_11") (pintype "passive"))
    )
    (net (code "28") (name "/VOUTS") (class "Default")
      (node (ref "C19") (pin "2") (pinfunction "2_2") (pintype "passive"))
      (node (ref "R14") (pin "2") (pinfunction "2_2") (pintype "passive"))
      (node (ref "R15") (pin "1") (pinfunction "1_1") (pintype "passive"))
      (node (ref "U2") (pin "3") (pinfunction "RC4_3") (pintype "passive"))
    )
    (net (code "29") (name "/VTANK") (class "Default")
      (node (ref "C1") (pin "1") (pinfunction "1_1") (pintype "passive"))
      (node (ref "C10") (pin "1") (pinfunction "1_1") (pintype "passive"))
      (node (ref "C2") (pin "1") (pinfunction "1_1") (pintype "passive"))
      (node (ref "C3") (pin "1") (pinfunction "1_1") (pintype "passive"))
      (node (ref "L4") (pin "2") (pinfunction "12_2") (pintype "passive"))
    )
    (net (code "30") (name "BAT+") (class "Default")
      (node (ref "C24") (pin "1") (pinfunction "1_1") (pintype "passive"))
      (node (ref "C6") (pin "2") (pinfunction "2_2") (pintype "passive"))
      (node (ref "Q4") (pin "4") (pinfunction "S_4") (pintype "passive"))
      (node (ref "Q6") (pin "1") (pinfunction "S_1") (pintype "passive"))
      (node (ref "Q6") (pin "2") (pinfunction "S_2") (pintype "passive"))
      (node (ref "Q6") (pin "3") (pinfunction "S_3") (pintype "passive"))
      (node (ref "R16") (pin "2") (pinfunction "2_2") (pintype "passive"))
      (node (ref "R25") (pin "1") (pinfunction "1_1") (pintype "passive"))
      (node (ref "R5") (pin "2") (pinfunction "2_2") (pintype "passive"))
      (node (ref "TP1") (pin "1") (pinfunction "1_1") (pintype "passive"))
      (node (ref "U3") (pin "1") (pinfunction "VIN_1") (pintype "passive"))
      (node (ref "U7") (pin "2") (pinfunction "CELL_2") (pintype "passive"))
      (node (ref "U7") (pin "3") (pinfunction "VDD_3") (pintype "passive"))
    )
    (net (code "31") (name "GND") (class "Default")
      (node (ref "C11") (pin "1") (pinfunction "1_1") (pintype "passive"))
      (node (ref "C12") (pin "1") (pinfunction "1_1") (pintype "passive"))
      (node (ref "C13") (pin "1") (pinfunction "1_1") (pintype "passive"))
      (node (ref "C14") (pin "1") (pinfunction "1_1") (pintype "passive"))
      (node (ref "C15") (pin "1") (pinfunction "1_1") (pintype "passive"))
      (node (ref "C16") (pin "1") (pinfunction "1_1") (pintype "passive"))
      (node (ref "C17") (pin "1") (pinfunction "1_1") (pintype "passive"))
      (node (ref "C18") (pin "1") (pinfunction "1_1") (pintype "passive"))
      (node (ref "C19") (pin "1") (pinfunction "1_1") (pintype "passive"))
      (node (ref "C20") (pin "1") (pinfunction "1_1") (pintype "passive"))
      (node (ref "C22") (pin "1") (pinfunction "1_1") (pintype "passive"))
      (node (ref "C23") (pin "1") (pinfunction "1_1") (pintype "passive"))
      (node (ref "C24") (pin "2") (pinfunction "2_2") (pintype "passive"))
      (node (ref "C25") (pin "2") (pinfunction "2_2") (pintype "passive"))
      (node (ref "C26") (pin "1") (pinfunction "1_1") (pintype "passive"))
      (node (ref "C27") (pin "1") (pinfunction "1_1") (pintype "passive"))
      (node (ref "C28") (pin "1") (pinfunction "1_1") (pintype "passive"))
      (node (ref "C29") (pin "1") (pinfunction "1_1") (pintype "passive"))
      (node (ref "C6") (pin "1") (pinfunction "1_1") (pintype "passive"))
      (node (ref "C9") (pin "1") (pinfunction "1_1") (pintype "passive"))
      (node (ref "J1") (pin "3") (pinfunction "3_3") (pintype "passive"))
      (node (ref "J2") (pin "4") (pinfunction "4_4") (pintype "passive"))
      (node (ref "Q1") (pin "2") (pinfunction "S_2") (pintype "passive"))
      (node (ref "Q2") (pin "2") (pinfunction "S_2") (pintype "passive"))
      (node (ref "Q3") (pin "2") (pinfunction "2_2") (pintype "passive"))
      (node (ref "Q3") (pin "3") (pinfunction "3_3") (pintype "passive"))
      (node (ref "Q5") (pin "2") (pinfunction "S_2") (pintype "passive"))
      (node (ref "Q7") (pin "2") (pinfunction "E_2") (pintype "passive"))
      (node (ref "R1") (pin "1") (pinfunction "1_1") (pintype "passive"))
      (node (ref "R10") (pin "1") (pinfunction "1_1") (pintype "passive"))
      (node (ref "R14") (pin "1") (pinfunction "1_1") (pintype "passive"))
      (node (ref "R17") (pin "1") (pinfunction "1_1") (pintype "passive"))
      (node (ref "R18") (pin "1") (pinfunction "1_1") (pintype "passive"))
      (node (ref "R22") (pin "1") (pinfunction "1_1") (pintype "passive"))
      (node (ref "R26") (pin "2") (pinfunction "2_2") (pintype "passive"))
      (node (ref "R27") (pin "2") (pinfunction "2_2") (pintype "passive"))
      (node (ref "R29") (pin "1") (pinfunction "1_1") (pintype "passive"))
      (node (ref "R3") (pin "1") (pinfunction "1_1") (pintype "passive"))
      (node (ref "R30") (pin "1") (pinfunction "1_1") (pintype "passive"))
      (node (ref "R4") (pin "1") (pinfunction "1_1") (pintype "passive"))
      (node (ref "R49") (pin "2") (pinfunction "2_2") (pintype "passive"))
      (node (ref "R7") (pin "1") (pinfunction "1_1") (pintype "passive"))
      (node (ref "S1") (pin "3") (pinfunction "2_3") (pintype "passive"))
      (node (ref "SW1") (pin "2") (pinfunction "2_2") (pintype "passive"))
      (node (ref "TP2") (pin "1") (pinfunction "1_1") (pintype "passive"))
      (node (ref "TP4") (pin "1") (pinfunction "1_1") (pintype "passive"))
      (node (ref "U1") (pin "1") (pinfunction "GND_1") (pintype "passive"))
      (node (ref "U2") (pin "17") (pinfunction "VSS_17") (pintype "passive"))
      (node (ref "U2") (pin "21") (pinfunction "VSS_21") (pintype "passive"))
      (node (ref "U3") (pin "2") (pinfunction "GND_2") (pintype "passive"))
      (node (ref "U4") (pin "2") (pinfunction "VSS_2") (pintype "passive"))
      (node (ref "U4") (pin "3") (pinfunction "VIN+_3") (pintype "passive"))
      (node (ref "U5") (pin "4") (pinfunction "GND_4") (pintype "passive"))
      (node (ref "U5") (pin "7") (pinfunction "FCCM_7") (pintype "passive"))
      (node (ref "U6") (pin "3") (pinfunction "GND_3") (pintype "passive"))
      (node (ref "U7") (pin "1") (pinfunction "CTG_1") (pintype "passive"))
      (node (ref "U7") (pin "4") (pinfunction "GND_4") (pintype "passive"))
      (node (ref "U7") (pin "9") (pinfunction "GND_9") (pintype "passive"))
      (node (ref "U8") (pin "5") (pinfunction "VSS/VSSA_5") (pintype "passive"))
    )
    (net (code "32") (name "Net-(C1-Pad2)") (class "Default")
      (node (ref "C1") (pin "2") (pinfunction "2_2") (pintype "passive"))
      (node (ref "C2") (pin "2") (pinfunction "2_2") (pintype "passive"))
      (node (ref "C3") (pin "2") (pinfunction "2_2") (pintype "passive"))
      (node (ref "C4") (pin "2") (pinfunction "2_2") (pintype "passive"))
      (node (ref "C5") (pin "1") (pinfunction "1_1") (pintype "passive"))
      (node (ref "D1") (pin "K") (pinfunction "K_K") (pintype "passive"))
      (node (ref "D2") (pin "A") (pinfunction "A_A") (pintype "passive"))
    )
    (net (code "33") (name "Net-(C10-Pad2)") (class "Default")
      (node (ref "C10") (pin "2") (pinfunction "2_2") (pintype "passive"))
      (node (ref "R6") (pin "2") (pinfunction "2_2") (pintype "passive"))
    )
    (net (code "34") (name "Net-(C17-Pad2)") (class "Default")
      (node (ref "C17") (pin "2") (pinfunction "2_2") (pintype "passive"))
      (node (ref "C18") (pin "2") (pinfunction "2_2") (pintype "passive"))
      (node (ref "L3") (pin "2") (pinfunction "2_2") (pintype "passive"))
      (node (ref "Q4") (pin "1") (pinfunction "D_1") (pintype "passive"))
      (node (ref "Q4") (pin "2") (pinfunction "D_2") (pintype "passive"))
      (node (ref "Q4") (pin "5") (pinfunction "D_5") (pintype "passive"))
      (node (ref "Q4") (pin "6") (pinfunction "D_6") (pintype "passive"))
      (node (ref "R15") (pin "2") (pinfunction "2_2") (pintype "passive"))
    )
    (net (code "35") (name "Net-(C20-Pad2)") (class "Default")
      (node (ref "C20") (pin "2") (pinfunction "2_2") (pintype "passive"))
      (node (ref "R20") (pin "2") (pinfunction "2_2") (pintype "passive"))
      (node (ref "R21") (pin "1") (pinfunction "1_1") (pintype "passive"))
    )
    (net (code "36") (name "Net-(D5--BLUE)") (class "Default")
      (node (ref "D5") (pin "4") (pinfunction "-BLUE_4") (pintype "passive"))
      (node (ref "R32") (pin "1") (pinfunction "1_1") (pintype "passive"))
    )
    (net (code "37") (name "Net-(D5--GREEN)") (class "Default")
      (node (ref "D5") (pin "3") (pinfunction "-GREEN_3") (pintype "passive"))
      (node (ref "R33") (pin "1") (pinfunction "1_1") (pintype "passive"))
    )
    (net (code "38") (name "Net-(D5--RED)") (class "Default")
      (node (ref "D5") (pin "2") (pinfunction "-RED_2") (pintype "passive"))
      (node (ref "R34") (pin "1") (pinfunction "1_1") (pintype "passive"))
    )
    (net (code "39") (name "Net-(D6-PadPOS)") (class "Default")
      (node (ref "D6") (pin "POS") (pinfunction "POS_POS") (pintype "passive"))
      (node (ref "Q3") (pin "1") (pinfunction "1_1") (pintype "passive"))
      (node (ref "R9") (pin "2") (pinfunction "2_2") (pintype "passive"))
    )
    (net (code "40") (name "Net-(L4-11)") (class "Default")
      (node (ref "C5") (pin "2") (pinfunction "2_2") (pintype "passive"))
      (node (ref "D3") (pin "K") (pinfunction "K_K") (pintype "passive"))
      (node (ref "D4") (pin "A") (pinfunction "A_A") (pintype "passive"))
      (node (ref "L4") (pin "1") (pinfunction "11_1") (pintype "passive"))
      (node (ref "Q2") (pin "3") (pinfunction "D_3") (pintype "passive"))
    )
    (net (code "41") (name "Net-(Q1-D)") (class "Default")
      (node (ref "C4") (pin "1") (pinfunction "1_1") (pintype "passive"))
      (node (ref "Q1") (pin "3") (pinfunction "D_3") (pintype "passive"))
    )
    (net (code "42") (name "Net-(Q4-G)") (class "Default")
      (node (ref "Q4") (pin "3") (pinfunction "G_3") (pintype "passive"))
      (node (ref "Q5") (pin "3") (pinfunction "D_3") (pintype "passive"))
      (node (ref "R16") (pin "1") (pinfunction "1_1") (pintype "passive"))
    )
    (net (code "43") (name "Net-(Q6-D)") (class "Default")
      (node (ref "Q6") (pin "5_6_7_8") (pinfunction "D_5_6_7_8") (pintype "passive"))
      (node (ref "R28") (pin "2") (pinfunction "2_2") (pintype "passive"))
      (node (ref "U6") (pin "1") (pinfunction "VIN+_1") (pintype "passive"))
    )
    (net (code "44") (name "Net-(Q6-G)") (class "Default")
      (node (ref "Q6") (pin "4") (pinfunction "G_4") (pintype "passive"))
      (node (ref "R12") (pin "1") (pinfunction "1_1") (pintype "passive"))
    )
    (net (code "45") (name "Net-(Q7-B)") (class "Default")
      (node (ref "Q7") (pin "1") (pinfunction "B_1") (pintype "passive"))
      (node (ref "R24") (pin "1") (pinfunction "1_1") (pintype "passive"))
      (node (ref "R26") (pin "1") (pinfunction "1_1") (pintype "passive"))
    )
    (net (code "46") (name "Net-(Q7-C)") (class "Default")
      (node (ref "Q7") (pin "3") (pinfunction "C_3") (pintype "passive"))
      (node (ref "R12") (pin "2") (pinfunction "2_2") (pintype "passive"))
      (node (ref "R5") (pin "1") (pinfunction "1_1") (pintype "passive"))
    )
    (net (code "47") (name "Net-(R35-Pad1)") (class "Default")
      (node (ref "R35") (pin "1") (pinfunction "1_1") (pintype "passive"))
      (node (ref "R56") (pin "1") (pinfunction "1_1") (pintype "passive"))
    )
    (net (code "48") (name "Net-(R36-Pad1)") (class "Default")
      (node (ref "R36") (pin "1") (pinfunction "1_1") (pintype "passive"))
      (node (ref "R57") (pin "1") (pinfunction "1_1") (pintype "passive"))
    )
    (net (code "49") (name "Net-(R40-Pad1)") (class "Default")
      (node (ref "R40") (pin "1") (pinfunction "1_1") (pintype "passive"))
      (node (ref "R41") (pin "2") (pinfunction "2_2") (pintype "passive"))
    )
    (net (code "50") (name "Net-(R43-Pad1)") (class "Default")
      (node (ref "R43") (pin "1") (pinfunction "1_1") (pintype "passive"))
      (node (ref "R44") (pin "2") (pinfunction "2_2") (pintype "passive"))
    )
    (net (code "51") (name "Net-(U2-RB4)") (class "Default")
      (node (ref "R38") (pin "1") (pinfunction "1_1") (pintype "passive"))
      (node (ref "U2") (pin "10") (pinfunction "RB4_10") (pintype "passive"))
    )
    (net (code "52") (name "Net-(U2-RB5)") (class "Default")
      (node (ref "R39") (pin "1") (pinfunction "1_1") (pintype "passive"))
      (node (ref "U2") (pin "9") (pinfunction "RB5_9") (pintype "passive"))
    )
    (net (code "53") (name "Net-(U2-RB6)") (class "Default")
      (node (ref "R42") (pin "1") (pinfunction "1_1") (pintype "passive"))
      (node (ref "U2") (pin "8") (pinfunction "RB6_8") (pintype "passive"))
    )
    (net (code "54") (name "Net-(U2-RB7)") (class "Default")
      (node (ref "R45") (pin "1") (pinfunction "1_1") (pintype "passive"))
      (node (ref "U2") (pin "7") (pinfunction "RB7_7") (pintype "passive"))
    )
    (net (code "55") (name "Net-(U2-RC3)") (class "Default")
      (node (ref "R2") (pin "2") (pinfunction "2_2") (pintype "passive"))
      (node (ref "R61") (pin "2") (pinfunction "2_2") (pintype "passive"))
      (node (ref "U2") (pin "4") (pinfunction "RC3_4") (pintype "passive"))
    )
    (net (code "56") (name "Net-(U2-RC5)") (class "Default")
      (node (ref "R48") (pin "1") (pinfunction "1_1") (pintype "passive"))
      (node (ref "U2") (pin "2") (pinfunction "RC5_2") (pintype "passive"))
    )
    (net (code "57") (name "Net-(U2-RC6)") (class "Default")
      (node (ref "R47") (pin "1") (pinfunction "1_1") (pintype "passive"))
      (node (ref "U2") (pin "5") (pinfunction "RC6_5") (pintype "passive"))
    )
    (net (code "58") (name "Net-(U2-RC7)") (class "Default")
      (node (ref "R46") (pin "1") (pinfunction "1_1") (pintype "passive"))
      (node (ref "U2") (pin "6") (pinfunction "RC7_6") (pintype "passive"))
    )
    (net (code "59") (name "Net-(U2-VDD)") (class "Default")
      (node (ref "R13") (pin "1") (pinfunction "1_1") (pintype "passive"))
      (node (ref "R37") (pin "1") (pinfunction "1_1") (pintype "passive"))
      (node (ref "U2") (pin "18") (pinfunction "VDD_18") (pintype "passive"))
    )
    (net (code "60") (name "Net-(U3-~{shutdown})") (class "Default")
      (node (ref "R25") (pin "2") (pinfunction "2_2") (pintype "passive"))
      (node (ref "U3") (pin "3") (pinfunction "~{shutdown}_3") (pintype "passive"))
    )
    (net (code "61") (name "Net-(U4-VIN-)") (class "Default")
      (node (ref "R19") (pin "1") (pinfunction "1_1") (pintype "passive"))
      (node (ref "R20") (pin "1") (pinfunction "1_1") (pintype "passive"))
      (node (ref "U4") (pin "4") (pinfunction "VIN-_4") (pintype "passive"))
    )
    (net (code "62") (name "Net-(U5-BOOT)") (class "Default")
      (node (ref "C21") (pin "2") (pinfunction "2_2") (pintype "passive"))
      (node (ref "U5") (pin "2") (pinfunction "BOOT_2") (pintype "passive"))
    )
    (net (code "63") (name "Net-(U6-A0)") (class "Default")
      (node (ref "R29") (pin "2") (pinfunction "2_2") (pintype "passive"))
      (node (ref "U6") (pin "7") (pinfunction "A0_7") (pintype "passive"))
    )
    (net (code "64") (name "Net-(U6-A1)") (class "Default")
      (node (ref "R30") (pin "2") (pinfunction "2_2") (pintype "passive"))
      (node (ref "U6") (pin "8") (pinfunction "A1_8") (pintype "passive"))
    )
    (net (code "65") (name "Net-(U6-VIN-)") (class "Default")
      (node (ref "R28") (pin "1") (pinfunction "1_1") (pintype "passive"))
      (node (ref "TP3") (pin "1") (pinfunction "1_1") (pintype "passive"))
      (node (ref "U6") (pin "2") (pinfunction "VIN-_2") (pintype "passive"))
    )
    (net (code "66") (name "Net-(U7-QSTRT)") (class "Default")
      (node (ref "R27") (pin "1") (pinfunction "1_1") (pintype "passive"))
      (node (ref "U7") (pin "6") (pinfunction "QSTRT_6") (pintype "passive"))
    )
    (net (code "67") (name "Net-(U8-PA0)") (class "Default")
      (node (ref "R50") (pin "2") (pinfunction "2_2") (pintype "passive"))
      (node (ref "U8") (pin "7") (pinfunction "PA0_7") (pintype "passive"))
    )
    (net (code "68") (name "Net-(U8-PA1)") (class "Default")
      (node (ref "R52") (pin "2") (pinfunction "2_2") (pintype "passive"))
      (node (ref "U8") (pin "8") (pinfunction "PA1_8") (pintype "passive"))
    )
    (net (code "69") (name "Net-(U8-PA2)") (class "Default")
      (node (ref "R53") (pin "2") (pinfunction "2_2") (pintype "passive"))
      (node (ref "U8") (pin "9") (pinfunction "PA2_9") (pintype "passive"))
    )
    (net (code "70") (name "Net-(U8-PA3)") (class "Default")
      (node (ref "R54") (pin "2") (pinfunction "2_2") (pintype "passive"))
      (node (ref "U8") (pin "10") (pinfunction "PA3_10") (pintype "passive"))
    )
    (net (code "71") (name "Net-(U8-PA4)") (class "Default")
      (node (ref "R55") (pin "2") (pinfunction "2_2") (pintype "passive"))
      (node (ref "U8") (pin "11") (pinfunction "PA4_11") (pintype "passive"))
    )
    (net (code "72") (name "Net-(U8-PA6)") (class "Default")
      (node (ref "R58") (pin "2") (pinfunction "2_2") (pintype "passive"))
      (node (ref "U8") (pin "13") (pinfunction "PA6_13") (pintype "passive"))
    )
    (net (code "73") (name "Net-(U8-PA11)") (class "Default")
      (node (ref "R59") (pin "2") (pinfunction "2_2") (pintype "passive"))
      (node (ref "U8") (pin "16") (pinfunction "PA11_16") (pintype "passive"))
    )
    (net (code "74") (name "Net-(U8-PA12)") (class "Default")
      (node (ref "R60") (pin "2") (pinfunction "2_2") (pintype "passive"))
      (node (ref "U8") (pin "17") (pinfunction "PA12_17") (pintype "passive"))
    )
    (net (code "75") (name "Net-(U8-PB0{slash}PB1{slash}PB2{slash}PA8)") (class "Default")
      (node (ref "R51") (pin "1") (pinfunction "1_1") (pintype "passive"))
      (node (ref "U8") (pin "15") (pinfunction "PB0/PB1/PB2/PA8_15") (pintype "passive"))
    )
    (net (code "76") (name "Net-(U8-PB3{slash}PB4{slash}PB5{slash}PB6)") (class "Default")
      (node (ref "TP5") (pin "1") (pinfunction "1_1") (pintype "passive"))
      (node (ref "U8") (pin "20") (pinfunction "PB3/PB4/PB5/PB6_20") (pintype "passive"))
    )
    (net (code "77") (name "Net-(U8-PB7{slash}PB8)") (class "Default")
      (node (ref "TP5") (pin "2") (pinfunction "2_2") (pintype "passive"))
      (node (ref "U8") (pin "1") (pinfunction "PB7/PB8_1") (pintype "passive"))
    )
    (net (code "78") (name "V-OR") (class "Default")
      (node (ref "C29") (pin "2") (pinfunction "2_2") (pintype "passive"))
      (node (ref "D7") (pin "2") (pinfunction "K_2") (pintype "passive"))
      (node (ref "Q8") (pin "2") (pinfunction "S_2") (pintype "passive"))
      (node (ref "R37") (pin "2") (pinfunction "2_2") (pintype "passive"))
      (node (ref "R40") (pin "2") (pinfunction "2_2") (pintype "passive"))
      (node (ref "R43") (pin "2") (pinfunction "2_2") (pintype "passive"))
    )
    (net (code "79") (name "VREC") (class "Default")
      (node (ref "C11") (pin "2") (pinfunction "2_2") (pintype "passive"))
      (node (ref "C7") (pin "2") (pinfunction "2_2") (pintype "passive"))
      (node (ref "C8") (pin "2") (pinfunction "2_2") (pintype "passive"))
      (node (ref "C9") (pin "2") (pinfunction "2_2") (pintype "passive"))
      (node (ref "D2") (pin "K") (pinfunction "K_K") (pintype "passive"))
      (node (ref "D4") (pin "K") (pinfunction "K_K") (pintype "passive"))
      (node (ref "Q3") (pin "8") (pinfunction "8_8") (pintype "passive"))
      (node (ref "R1") (pin "2") (pinfunction "2_2") (pintype "passive"))
      (node (ref "R8") (pin "2") (pinfunction "2_2") (pintype "passive"))
      (node (ref "U1") (pin "3") (pinfunction "VIN_3") (pintype "passive"))
    )
    (net (code "80") (name "unconnected-(S1-1-Pad2)") (class "Default")
      (node (ref "S1") (pin "2") (pinfunction "1_2") (pintype "passive"))
    )
    (net (code "81") (name "unconnected-(S1-2-Pad4)") (class "Default")
      (node (ref "S1") (pin "4") (pinfunction "2_4") (pintype "passive"))
    )
    (net (code "82") (name "unconnected-(U3-NC{slash}ADJ-Pad4)") (class "Default")
      (node (ref "U3") (pin "4") (pinfunction "NC/ADJ_4") (pintype "passive+no_connect"))
    )
    (net (code "83") (name "unconnected-(U8-PA5-Pad12)") (class "Default")
      (node (ref "U8") (pin "12") (pinfunction "PA5_12") (pintype "passive+no_connect"))
    )
    (net (code "84") (name "unconnected-(U8-PA7-Pad14)") (class "Default")
      (node (ref "U8") (pin "14") (pinfunction "PA7_14") (pintype "passive+no_connect"))
    )
    (net (code "85") (name "unconnected-(U8-PB9{slash}PC14-OSC32_IN-Pad2)") (class "Default")
      (node (ref "U8") (pin "2") (pinfunction "PB9/PC14-OSC32_IN_2") (pintype "passive+no_connect"))
    )
    (net (code "86") (name "unconnected-(U8-PC15-OSC32_OUT-Pad3)") (class "Default")
      (node (ref "U8") (pin "3") (pinfunction "PC15-OSC32_OUT_3") (pintype "passive+no_connect"))
    )
  )
)
